# BMS_Slave_R2.net
KiCad netlist of a schematic drawn in Altium Designer
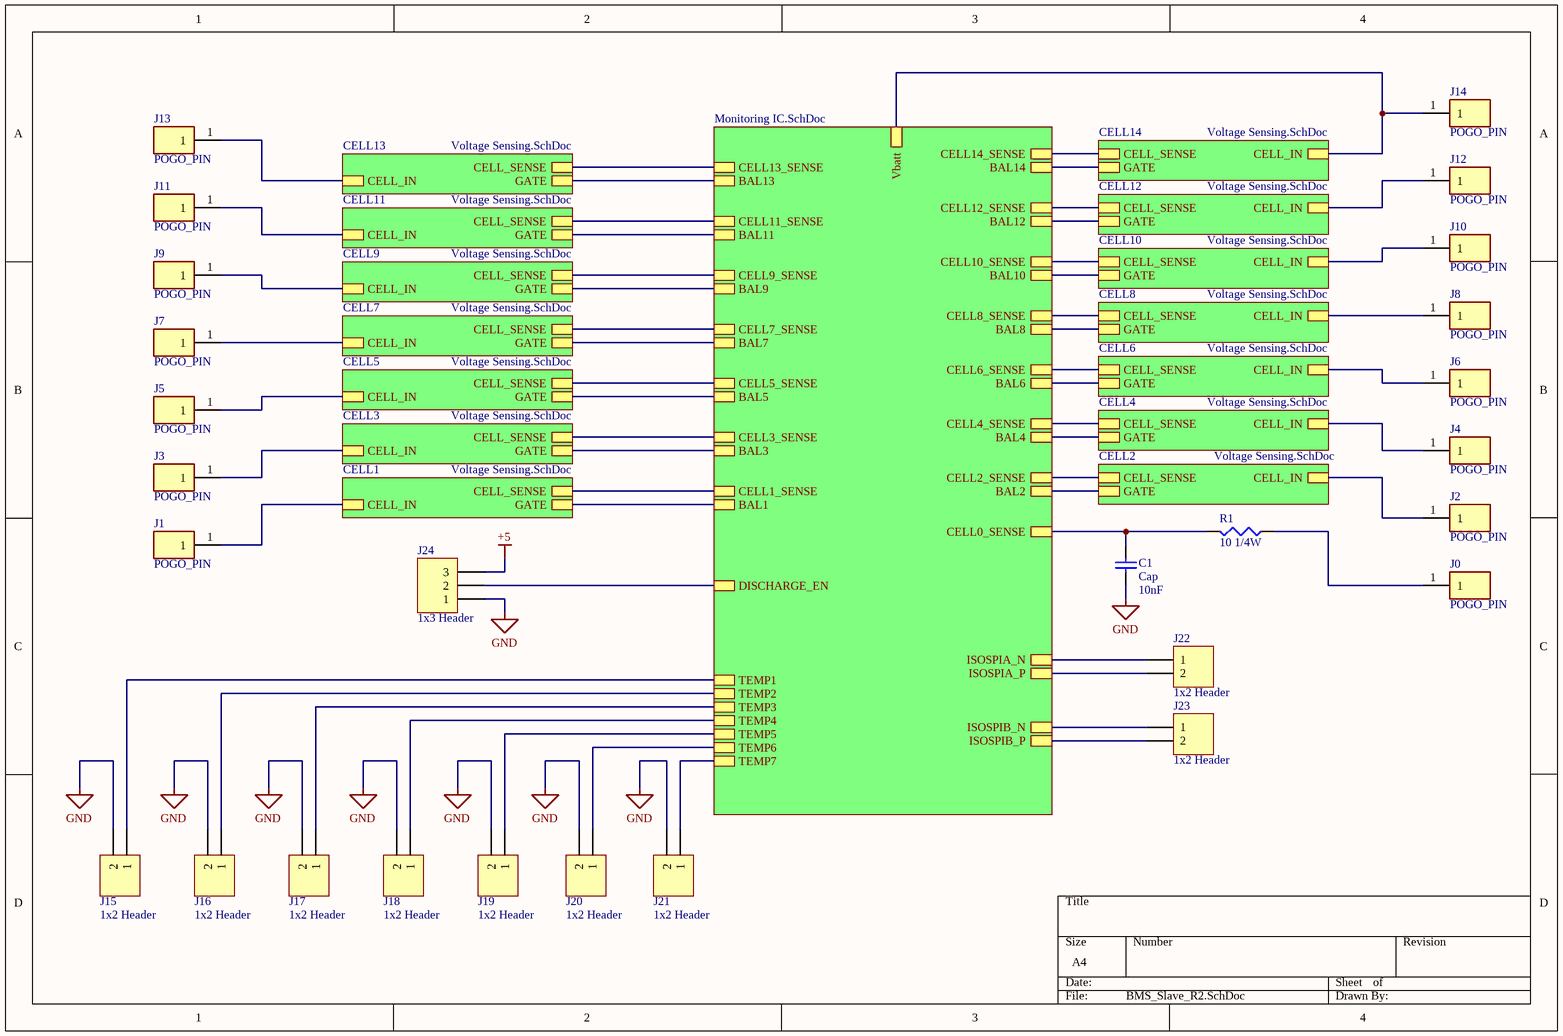
[diagram p0: BMS_Slave_R2.SchDoc]

(export (version "E")
  (design (tool "Eeschema 10.0.6"))
  (components
    (comp (ref "C1")
      (value "Cap")
      (footprint "0603 - Capacitor")
      (description "Capacitor")
      (fields (field (name "ALTIUM_VALUE") "10nF") (field (name "PUBLISHER") "Altium Limited"))
      (libsource (lib "Miscellaneous Devices") (part "Cap"))
    )
    (comp (ref "J0")
      (value "POGO_PIN")
      (footprint "POGO_PIN")
      (description "Pogo Pin")
      (libsource (lib "BMS Slave Device R2") (part "POGO_PIN"))
    )
    (comp (ref "J1")
      (value "POGO_PIN")
      (footprint "POGO_PIN")
      (description "Pogo Pin")
      (libsource (lib "") (part "POGO_PIN_1"))
    )
    (comp (ref "J2")
      (value "POGO_PIN")
      (footprint "POGO_PIN")
      (description "Pogo Pin")
      (libsource (lib "BMS Slave Device R2") (part "POGO_PIN"))
    )
    (comp (ref "J3")
      (value "POGO_PIN")
      (footprint "POGO_PIN")
      (description "Pogo Pin")
      (libsource (lib "") (part "POGO_PIN_1"))
    )
    (comp (ref "J4")
      (value "POGO_PIN")
      (footprint "POGO_PIN")
      (description "Pogo Pin")
      (libsource (lib "BMS Slave Device R2") (part "POGO_PIN"))
    )
    (comp (ref "J5")
      (value "POGO_PIN")
      (footprint "POGO_PIN")
      (description "Pogo Pin")
      (libsource (lib "") (part "POGO_PIN_1"))
    )
    (comp (ref "J6")
      (value "POGO_PIN")
      (footprint "POGO_PIN")
      (description "Pogo Pin")
      (libsource (lib "BMS Slave Device R2") (part "POGO_PIN"))
    )
    (comp (ref "J7")
      (value "POGO_PIN")
      (footprint "POGO_PIN")
      (description "Pogo Pin")
      (libsource (lib "") (part "POGO_PIN_1"))
    )
    (comp (ref "J8")
      (value "POGO_PIN")
      (footprint "POGO_PIN")
      (description "Pogo Pin")
      (libsource (lib "BMS Slave Device R2") (part "POGO_PIN"))
    )
    (comp (ref "J9")
      (value "POGO_PIN")
      (footprint "POGO_PIN")
      (description "Pogo Pin")
      (libsource (lib "") (part "POGO_PIN_1"))
    )
    (comp (ref "J10")
      (value "POGO_PIN")
      (footprint "POGO_PIN")
      (description "Pogo Pin")
      (libsource (lib "BMS Slave Device R2") (part "POGO_PIN"))
    )
    (comp (ref "J11")
      (value "POGO_PIN")
      (footprint "POGO_PIN")
      (description "Pogo Pin")
      (libsource (lib "") (part "POGO_PIN_1"))
    )
    (comp (ref "J12")
      (value "POGO_PIN")
      (footprint "POGO_PIN")
      (description "Pogo Pin")
      (libsource (lib "BMS Slave Device R2") (part "POGO_PIN"))
    )
    (comp (ref "J13")
      (value "POGO_PIN")
      (footprint "POGO_PIN")
      (description "Pogo Pin")
      (libsource (lib "") (part "POGO_PIN_1"))
    )
    (comp (ref "J14")
      (value "POGO_PIN")
      (footprint "POGO_PIN")
      (description "Pogo Pin")
      (libsource (lib "BMS Slave Device R2") (part "POGO_PIN"))
    )
    (comp (ref "J15")
      (value "1x2 Header")
      (footprint "HDR1X2")
      (description "1x2 Pin Header")
      (libsource (lib "GeneralConnectors") (part "1x2 Header"))
    )
    (comp (ref "J16")
      (value "1x2 Header")
      (footprint "HDR1X2")
      (description "1x2 Pin Header")
      (libsource (lib "GeneralConnectors") (part "1x2 Header"))
    )
    (comp (ref "J17")
      (value "1x2 Header")
      (footprint "HDR1X2")
      (description "1x2 Pin Header")
      (libsource (lib "GeneralConnectors") (part "1x2 Header"))
    )
    (comp (ref "J18")
      (value "1x2 Header")
      (footprint "HDR1X2")
      (description "1x2 Pin Header")
      (libsource (lib "GeneralConnectors") (part "1x2 Header"))
    )
    (comp (ref "J19")
      (value "1x2 Header")
      (footprint "HDR1X2")
      (description "1x2 Pin Header")
      (libsource (lib "GeneralConnectors") (part "1x2 Header"))
    )
    (comp (ref "J20")
      (value "1x2 Header")
      (footprint "HDR1X2")
      (description "1x2 Pin Header")
      (libsource (lib "GeneralConnectors") (part "1x2 Header"))
    )
    (comp (ref "J21")
      (value "1x2 Header")
      (footprint "HDR1X2")
      (description "1x2 Pin Header")
      (libsource (lib "GeneralConnectors") (part "1x2 Header"))
    )
    (comp (ref "J22")
      (value "1x2 Header")
      (footprint "B2BXH2LFSN")
      (description "1x2 Pin Header")
      (libsource (lib "") (part "1x2 Header_1"))
    )
    (comp (ref "J23")
      (value "1x2 Header")
      (footprint "B2BXH2LFSN")
      (description "1x2 Pin Header")
      (libsource (lib "") (part "1x2 Header_1"))
    )
    (comp (ref "J24")
      (value "1x3 Header")
      (footprint "HDR1X3")
      (description "1x3 Pin Header")
      (libsource (lib "GeneralConnectors") (part "1x3 Header"))
    )
    (comp (ref "R1")
      (value "10 1/4W")
      (footprint "0805 - Resistor")
      (description "Resistor")
      (fields (field (name "Comment") "Res3") (field (name "PUBLISHER") "Altium Limited"))
      (libsource (lib "Miscellaneous Devices") (part "Res3"))
    )
  )
  (nets
    (net (code "1") (name "+5") (class "Default")
      (node (ref "J24") (pin "3") (pinfunction "3_3") (pintype "passive"))
    )
    (net (code "16") (name "/CELL0_SENSE") (class "Default")
      (node (ref "C1") (pin "2") (pinfunction "2_2") (pintype "passive"))
      (node (ref "R1") (pin "1") (pinfunction "1_1") (pintype "passive"))
    )
    (net (code "31") (name "/CELL_IN") (class "Default")
      (node (ref "J4") (pin "1") (pinfunction "1_1") (pintype "passive"))
    )
    (net (code "32") (name "/CELL_IN_1") (class "Default")
      (node (ref "J9") (pin "1") (pinfunction "1_1") (pintype "passive"))
    )
    (net (code "33") (name "/CELL_IN_2") (class "Default")
      (node (ref "J7") (pin "1") (pinfunction "1_1") (pintype "passive"))
    )
    (net (code "34") (name "/CELL_IN_3") (class "Default")
      (node (ref "J13") (pin "1") (pinfunction "1_1") (pintype "passive"))
    )
    (net (code "35") (name "/CELL_IN_4") (class "Default")
      (node (ref "J11") (pin "1") (pinfunction "1_1") (pintype "passive"))
    )
    (net (code "36") (name "/CELL_IN_5") (class "Default")
      (node (ref "J5") (pin "1") (pinfunction "1_1") (pintype "passive"))
    )
    (net (code "37") (name "/CELL_IN_6") (class "Default")
      (node (ref "J3") (pin "1") (pinfunction "1_1") (pintype "passive"))
    )
    (net (code "38") (name "/CELL_IN_7") (class "Default")
      (node (ref "J14") (pin "1") (pinfunction "1_1") (pintype "passive"))
    )
    (net (code "39") (name "/CELL_IN_8") (class "Default")
      (node (ref "J1") (pin "1") (pinfunction "1_1") (pintype "passive"))
    )
    (net (code "40") (name "/CELL_IN_9") (class "Default")
      (node (ref "J12") (pin "1") (pinfunction "1_1") (pintype "passive"))
    )
    (net (code "41") (name "/CELL_IN_10") (class "Default")
      (node (ref "J10") (pin "1") (pinfunction "1_1") (pintype "passive"))
    )
    (net (code "42") (name "/CELL_IN_11") (class "Default")
      (node (ref "J8") (pin "1") (pinfunction "1_1") (pintype "passive"))
    )
    (net (code "43") (name "/CELL_IN_12") (class "Default")
      (node (ref "J2") (pin "1") (pinfunction "1_1") (pintype "passive"))
    )
    (net (code "44") (name "/CELL_IN_13") (class "Default")
      (node (ref "J6") (pin "1") (pinfunction "1_1") (pintype "passive"))
    )
    (net (code "45") (name "/DISCHARGE_EN") (class "Default")
      (node (ref "J24") (pin "2") (pinfunction "2_2") (pintype "passive"))
    )
    (net (code "46") (name "/ISOSPIA_N") (class "Default")
      (node (ref "J22") (pin "1") (pinfunction "1_1") (pintype "passive"))
    )
    (net (code "47") (name "/ISOSPIA_P") (class "Default")
      (node (ref "J22") (pin "2") (pinfunction "2_2") (pintype "passive"))
    )
    (net (code "48") (name "/ISOSPIB_N") (class "Default")
      (node (ref "J23") (pin "1") (pinfunction "1_1") (pintype "passive"))
    )
    (net (code "49") (name "/ISOSPIB_P") (class "Default")
      (node (ref "J23") (pin "2") (pinfunction "2_2") (pintype "passive"))
    )
    (net (code "50") (name "/TEMP1") (class "Default")
      (node (ref "J15") (pin "1") (pinfunction "1_1") (pintype "passive"))
    )
    (net (code "51") (name "/TEMP2") (class "Default")
      (node (ref "J16") (pin "1") (pinfunction "1_1") (pintype "passive"))
    )
    (net (code "52") (name "/TEMP3") (class "Default")
      (node (ref "J17") (pin "1") (pinfunction "1_1") (pintype "passive"))
    )
    (net (code "53") (name "/TEMP4") (class "Default")
      (node (ref "J18") (pin "1") (pinfunction "1_1") (pintype "passive"))
    )
    (net (code "54") (name "/TEMP5") (class "Default")
      (node (ref "J19") (pin "1") (pinfunction "1_1") (pintype "passive"))
    )
    (net (code "55") (name "/TEMP6") (class "Default")
      (node (ref "J20") (pin "1") (pinfunction "1_1") (pintype "passive"))
    )
    (net (code "56") (name "/TEMP7") (class "Default")
      (node (ref "J21") (pin "1") (pinfunction "1_1") (pintype "passive"))
    )
    (net (code "57") (name "GND") (class "Default")
      (node (ref "C1") (pin "1") (pinfunction "1_1") (pintype "passive"))
      (node (ref "J15") (pin "2") (pinfunction "2_2") (pintype "passive"))
      (node (ref "J16") (pin "2") (pinfunction "2_2") (pintype "passive"))
      (node (ref "J17") (pin "2") (pinfunction "2_2") (pintype "passive"))
      (node (ref "J18") (pin "2") (pinfunction "2_2") (pintype "passive"))
      (node (ref "J19") (pin "2") (pinfunction "2_2") (pintype "passive"))
      (node (ref "J20") (pin "2") (pinfunction "2_2") (pintype "passive"))
      (node (ref "J21") (pin "2") (pinfunction "2_2") (pintype "passive"))
      (node (ref "J24") (pin "1") (pinfunction "1_1") (pintype "passive"))
    )
    (net (code "58") (name "Net-(J0-Pad1)") (class "Default")
      (node (ref "J0") (pin "1") (pinfunction "1_1") (pintype "passive"))
      (node (ref "R1") (pin "2") (pinfunction "2_2") (pintype "passive"))
    )
  )
)
